# mainboard.net
KiCad netlist of a schematic drawn in EAGLE
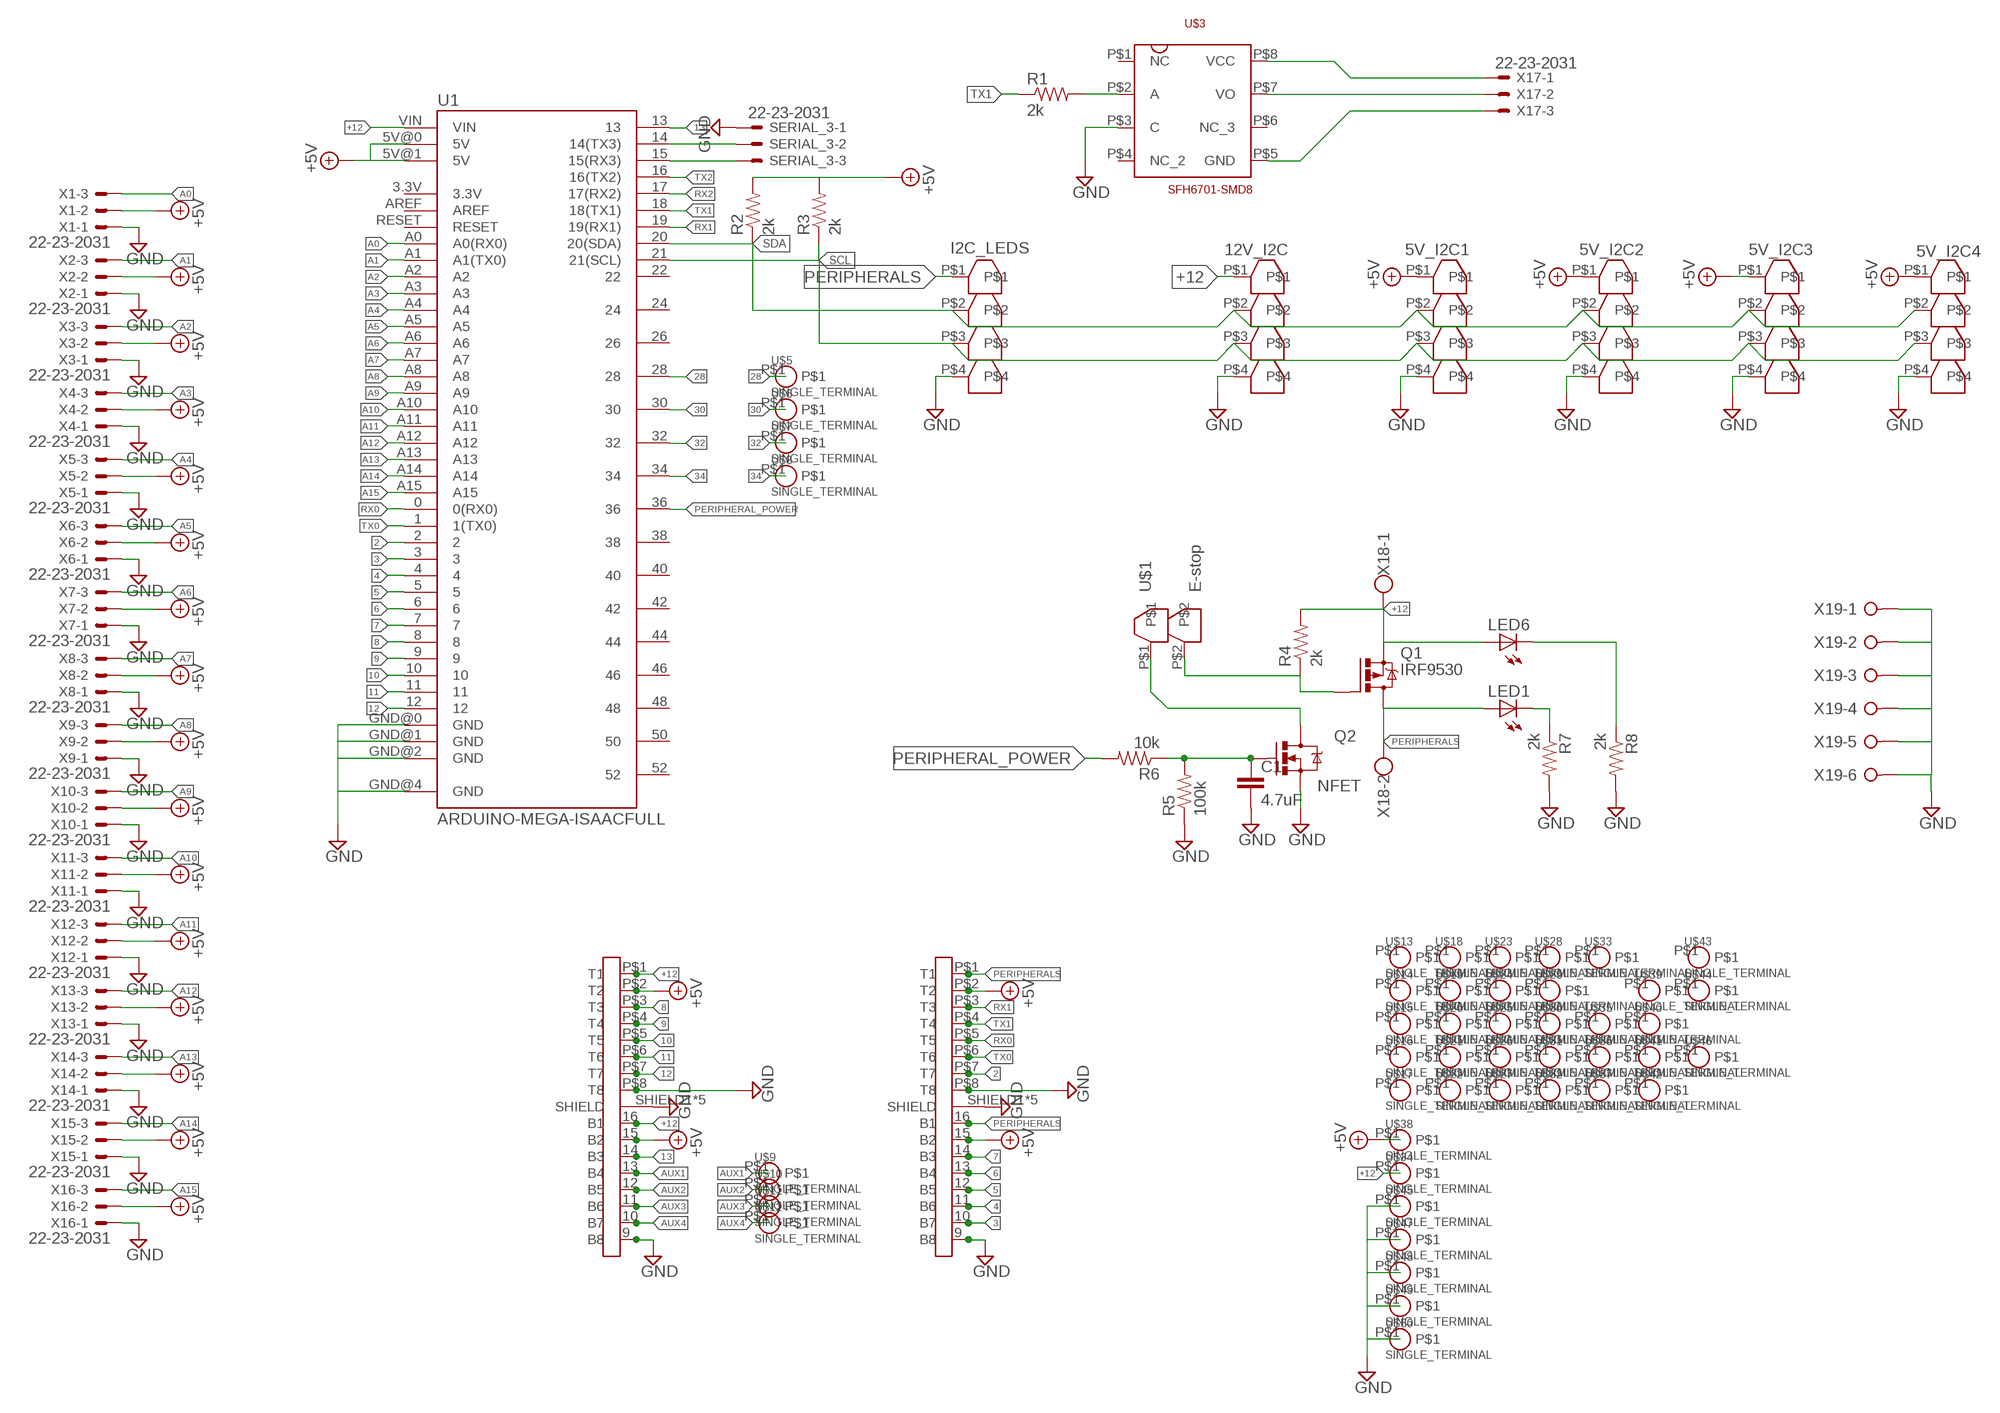
[diagram p0: schematic, sheet 1]

(export (version "E")
  (design (tool "Eeschema 10.0.6"))
  (components
    (comp (ref "5V_I2C1")
      (value "SCREW_TERMINAL_4")
      (footprint "eagle-import:SCREW_TERMINAL_4")
      (libsource (lib "eagle-import") (part "SCREW_TERMINAL_4"))
    )
    (comp (ref "5V_I2C2")
      (value "SCREW_TERMINAL_4")
      (footprint "eagle-import:SCREW_TERMINAL_4")
      (libsource (lib "eagle-import") (part "SCREW_TERMINAL_4"))
    )
    (comp (ref "5V_I2C3")
      (value "SCREW_TERMINAL_4")
      (footprint "eagle-import:SCREW_TERMINAL_4")
      (libsource (lib "eagle-import") (part "SCREW_TERMINAL_4"))
    )
    (comp (ref "5V_I2C4")
      (value "SCREW_TERMINAL_4")
      (footprint "eagle-import:SCREW_TERMINAL_4")
      (libsource (lib "eagle-import") (part "SCREW_TERMINAL_4"))
    )
    (comp (ref "12V_I2C")
      (value "SCREW_TERMINAL_4")
      (footprint "eagle-import:SCREW_TERMINAL_4")
      (libsource (lib "eagle-import") (part "SCREW_TERMINAL_4"))
    )
    (comp (ref "C1")
      (value "4.7uF")
      (footprint "eagle-import:C0603")
      (libsource (lib "eagle-import") (part "C-EUC0603"))
    )
    (comp (ref "I2C_LEDS")
      (value "SCREW_TERMINAL_4")
      (footprint "eagle-import:SCREW_TERMINAL_4")
      (libsource (lib "eagle-import") (part "SCREW_TERMINAL_4"))
    )
    (comp (ref "LED1")
      (value "LED0603")
      (footprint "eagle-import:LED-0603")
      (libsource (lib "eagle-import") (part "LED0603"))
    )
    (comp (ref "LED6")
      (value "LED0603")
      (footprint "eagle-import:LED-0603")
      (libsource (lib "eagle-import") (part "LED0603"))
    )
    (comp (ref "Q1")
      (value "IRF9530")
      (footprint "eagle-import:TO220BV")
      (libsource (lib "eagle-import") (part "IRF9530"))
    )
    (comp (ref "Q2")
      (value "NFET")
      (footprint "eagle-import:SOT23")
      (libsource (lib "eagle-import") (part "MOSFET-NCHANNELBSS123LT1G"))
    )
    (comp (ref "R1")
      (value "2k")
      (footprint "eagle-import:0603-RES")
      (libsource (lib "eagle-import") (part "RESISTOR0603-RES"))
    )
    (comp (ref "R2")
      (value "2k")
      (footprint "eagle-import:0603-RES")
      (libsource (lib "eagle-import") (part "RESISTOR0603-RES"))
    )
    (comp (ref "R3")
      (value "2k")
      (footprint "eagle-import:0603-RES")
      (libsource (lib "eagle-import") (part "RESISTOR0603-RES"))
    )
    (comp (ref "R4")
      (value "2k")
      (footprint "eagle-import:0603-RES")
      (libsource (lib "eagle-import") (part "RESISTOR0603-RES"))
    )
    (comp (ref "R5")
      (value "100k")
      (footprint "eagle-import:0603-RES")
      (libsource (lib "eagle-import") (part "RESISTOR0603-RES"))
    )
    (comp (ref "R6")
      (value "10k")
      (footprint "eagle-import:0603-RES")
      (libsource (lib "eagle-import") (part "RESISTOR0603-RES"))
    )
    (comp (ref "R7")
      (value "2k")
      (footprint "eagle-import:0603-RES")
      (libsource (lib "eagle-import") (part "RESISTOR0603-RES"))
    )
    (comp (ref "R8")
      (value "2k")
      (footprint "eagle-import:0603-RES")
      (libsource (lib "eagle-import") (part "RESISTOR0603-RES"))
    )
    (comp (ref "SERIAL_3")
      (value "22-23-2031")
      (footprint "eagle-import:22-23-2031")
      (fields
        (field (name "MF") "MOLEX")
        (field (name "MF_1") "MOLEX")
        (field (name "MPN") "22-23-2031")
        (field (name "OC_FARNELL") "1462950")
        (field (name "OC_NEWARK") "30C0862")
      )
      (libsource (lib "eagle-import") (part "22-23-2031"))
    )
    (comp (ref "U$1")
      (value "E-stop")
      (footprint "eagle-import:SCREW_TERMINAL_2")
      (libsource (lib "eagle-import") (part "SCREW_TERMINAL_2"))
    )
    (comp (ref "U$2")
      (value "RJ45-DUAL-STACKED")
      (footprint "eagle-import:RJ45-DUAL-10118096")
      (libsource (lib "eagle-import") (part "RJ45-DUAL-STACKED"))
    )
    (comp (ref "U$3")
      (value "SFH6701-SMD8")
      (footprint "eagle-import:8-SMD-GULLWING")
      (libsource (lib "eagle-import") (part "SFH6701-SMD8"))
    )
    (comp (ref "U$4")
      (value "RJ45-DUAL-STACKED")
      (footprint "eagle-import:RJ45-DUAL-10118096")
      (libsource (lib "eagle-import") (part "RJ45-DUAL-STACKED"))
    )
    (comp (ref "U$5")
      (value "SINGLE_TERMINAL")
      (footprint "eagle-import:PLATED_HOLE")
      (libsource (lib "eagle-import") (part "SINGLE_TERMINAL"))
    )
    (comp (ref "U$6")
      (value "SINGLE_TERMINAL")
      (footprint "eagle-import:PLATED_HOLE")
      (libsource (lib "eagle-import") (part "SINGLE_TERMINAL"))
    )
    (comp (ref "U$7")
      (value "SINGLE_TERMINAL")
      (footprint "eagle-import:PLATED_HOLE")
      (libsource (lib "eagle-import") (part "SINGLE_TERMINAL"))
    )
    (comp (ref "U$8")
      (value "SINGLE_TERMINAL")
      (footprint "eagle-import:PLATED_HOLE")
      (libsource (lib "eagle-import") (part "SINGLE_TERMINAL"))
    )
    (comp (ref "U$9")
      (value "SINGLE_TERMINAL")
      (footprint "eagle-import:PLATED_HOLE")
      (libsource (lib "eagle-import") (part "SINGLE_TERMINAL"))
    )
    (comp (ref "U$10")
      (value "SINGLE_TERMINAL")
      (footprint "eagle-import:PLATED_HOLE")
      (libsource (lib "eagle-import") (part "SINGLE_TERMINAL"))
    )
    (comp (ref "U$11")
      (value "SINGLE_TERMINAL")
      (footprint "eagle-import:PLATED_HOLE")
      (libsource (lib "eagle-import") (part "SINGLE_TERMINAL"))
    )
    (comp (ref "U$12")
      (value "SINGLE_TERMINAL")
      (footprint "eagle-import:PLATED_HOLE")
      (libsource (lib "eagle-import") (part "SINGLE_TERMINAL"))
    )
    (comp (ref "U$13")
      (value "SINGLE_TERMINAL")
      (footprint "eagle-import:PLATED_HOLE")
      (libsource (lib "eagle-import") (part "SINGLE_TERMINAL"))
    )
    (comp (ref "U$14")
      (value "SINGLE_TERMINAL")
      (footprint "eagle-import:PLATED_HOLE")
      (libsource (lib "eagle-import") (part "SINGLE_TERMINAL"))
    )
    (comp (ref "U$15")
      (value "SINGLE_TERMINAL")
      (footprint "eagle-import:PLATED_HOLE")
      (libsource (lib "eagle-import") (part "SINGLE_TERMINAL"))
    )
    (comp (ref "U$16")
      (value "SINGLE_TERMINAL")
      (footprint "eagle-import:PLATED_HOLE")
      (libsource (lib "eagle-import") (part "SINGLE_TERMINAL"))
    )
    (comp (ref "U$17")
      (value "SINGLE_TERMINAL")
      (footprint "eagle-import:PLATED_HOLE")
      (libsource (lib "eagle-import") (part "SINGLE_TERMINAL"))
    )
    (comp (ref "U$18")
      (value "SINGLE_TERMINAL")
      (footprint "eagle-import:PLATED_HOLE")
      (libsource (lib "eagle-import") (part "SINGLE_TERMINAL"))
    )
    (comp (ref "U$19")
      (value "SINGLE_TERMINAL")
      (footprint "eagle-import:PLATED_HOLE")
      (libsource (lib "eagle-import") (part "SINGLE_TERMINAL"))
    )
    (comp (ref "U$20")
      (value "SINGLE_TERMINAL")
      (footprint "eagle-import:PLATED_HOLE")
      (libsource (lib "eagle-import") (part "SINGLE_TERMINAL"))
    )
    (comp (ref "U$21")
      (value "SINGLE_TERMINAL")
      (footprint "eagle-import:PLATED_HOLE")
      (libsource (lib "eagle-import") (part "SINGLE_TERMINAL"))
    )
    (comp (ref "U$22")
      (value "SINGLE_TERMINAL")
      (footprint "eagle-import:PLATED_HOLE")
      (libsource (lib "eagle-import") (part "SINGLE_TERMINAL"))
    )
    (comp (ref "U$23")
      (value "SINGLE_TERMINAL")
      (footprint "eagle-import:PLATED_HOLE")
      (libsource (lib "eagle-import") (part "SINGLE_TERMINAL"))
    )
    (comp (ref "U$24")
      (value "SINGLE_TERMINAL")
      (footprint "eagle-import:PLATED_HOLE")
      (libsource (lib "eagle-import") (part "SINGLE_TERMINAL"))
    )
    (comp (ref "U$25")
      (value "SINGLE_TERMINAL")
      (footprint "eagle-import:PLATED_HOLE")
      (libsource (lib "eagle-import") (part "SINGLE_TERMINAL"))
    )
    (comp (ref "U$26")
      (value "SINGLE_TERMINAL")
      (footprint "eagle-import:PLATED_HOLE")
      (libsource (lib "eagle-import") (part "SINGLE_TERMINAL"))
    )
    (comp (ref "U$27")
      (value "SINGLE_TERMINAL")
      (footprint "eagle-import:PLATED_HOLE")
      (libsource (lib "eagle-import") (part "SINGLE_TERMINAL"))
    )
    (comp (ref "U$28")
      (value "SINGLE_TERMINAL")
      (footprint "eagle-import:PLATED_HOLE")
      (libsource (lib "eagle-import") (part "SINGLE_TERMINAL"))
    )
    (comp (ref "U$29")
      (value "SINGLE_TERMINAL")
      (footprint "eagle-import:PLATED_HOLE")
      (libsource (lib "eagle-import") (part "SINGLE_TERMINAL"))
    )
    (comp (ref "U$30")
      (value "SINGLE_TERMINAL")
      (footprint "eagle-import:PLATED_HOLE")
      (libsource (lib "eagle-import") (part "SINGLE_TERMINAL"))
    )
    (comp (ref "U$31")
      (value "SINGLE_TERMINAL")
      (footprint "eagle-import:PLATED_HOLE")
      (libsource (lib "eagle-import") (part "SINGLE_TERMINAL"))
    )
    (comp (ref "U$32")
      (value "SINGLE_TERMINAL")
      (footprint "eagle-import:PLATED_HOLE")
      (libsource (lib "eagle-import") (part "SINGLE_TERMINAL"))
    )
    (comp (ref "U$33")
      (value "SINGLE_TERMINAL")
      (footprint "eagle-import:PLATED_HOLE")
      (libsource (lib "eagle-import") (part "SINGLE_TERMINAL"))
    )
    (comp (ref "U$34")
      (value "SINGLE_TERMINAL")
      (footprint "eagle-import:PLATED_HOLE")
      (libsource (lib "eagle-import") (part "SINGLE_TERMINAL"))
    )
    (comp (ref "U$35")
      (value "SINGLE_TERMINAL")
      (footprint "eagle-import:PLATED_HOLE")
      (libsource (lib "eagle-import") (part "SINGLE_TERMINAL"))
    )
    (comp (ref "U$36")
      (value "SINGLE_TERMINAL")
      (footprint "eagle-import:PLATED_HOLE")
      (libsource (lib "eagle-import") (part "SINGLE_TERMINAL"))
    )
    (comp (ref "U$37")
      (value "SINGLE_TERMINAL")
      (footprint "eagle-import:PLATED_HOLE")
      (libsource (lib "eagle-import") (part "SINGLE_TERMINAL"))
    )
    (comp (ref "U$38")
      (value "SINGLE_TERMINAL")
      (footprint "eagle-import:PLATED_HOLE")
      (libsource (lib "eagle-import") (part "SINGLE_TERMINAL"))
    )
    (comp (ref "U$39")
      (value "SINGLE_TERMINAL")
      (footprint "eagle-import:PLATED_HOLE")
      (libsource (lib "eagle-import") (part "SINGLE_TERMINAL"))
    )
    (comp (ref "U$40")
      (value "SINGLE_TERMINAL")
      (footprint "eagle-import:PLATED_HOLE")
      (libsource (lib "eagle-import") (part "SINGLE_TERMINAL"))
    )
    (comp (ref "U$41")
      (value "SINGLE_TERMINAL")
      (footprint "eagle-import:PLATED_HOLE")
      (libsource (lib "eagle-import") (part "SINGLE_TERMINAL"))
    )
    (comp (ref "U$42")
      (value "SINGLE_TERMINAL")
      (footprint "eagle-import:PLATED_HOLE")
      (libsource (lib "eagle-import") (part "SINGLE_TERMINAL"))
    )
    (comp (ref "U$43")
      (value "SINGLE_TERMINAL")
      (footprint "eagle-import:PLATED_HOLE")
      (libsource (lib "eagle-import") (part "SINGLE_TERMINAL"))
    )
    (comp (ref "U$44")
      (value "SINGLE_TERMINAL")
      (footprint "eagle-import:PLATED_HOLE")
      (libsource (lib "eagle-import") (part "SINGLE_TERMINAL"))
    )
    (comp (ref "U$45")
      (value "SINGLE_TERMINAL")
      (footprint "eagle-import:PLATED_HOLE")
      (libsource (lib "eagle-import") (part "SINGLE_TERMINAL"))
    )
    (comp (ref "U$46")
      (value "SINGLE_TERMINAL")
      (footprint "eagle-import:PLATED_HOLE")
      (libsource (lib "eagle-import") (part "SINGLE_TERMINAL"))
    )
    (comp (ref "U$47")
      (value "SINGLE_TERMINAL")
      (footprint "eagle-import:PLATED_HOLE")
      (libsource (lib "eagle-import") (part "SINGLE_TERMINAL"))
    )
    (comp (ref "U$48")
      (value "SINGLE_TERMINAL")
      (footprint "eagle-import:PLATED_HOLE")
      (libsource (lib "eagle-import") (part "SINGLE_TERMINAL"))
    )
    (comp (ref "U$49")
      (value "SINGLE_TERMINAL")
      (footprint "eagle-import:PLATED_HOLE")
      (libsource (lib "eagle-import") (part "SINGLE_TERMINAL"))
    )
    (comp (ref "U$50")
      (value "SINGLE_TERMINAL")
      (footprint "eagle-import:PLATED_HOLE")
      (libsource (lib "eagle-import") (part "SINGLE_TERMINAL"))
    )
    (comp (ref "U1")
      (value "ARDUINO-MEGA-ISAACFULL")
      (footprint "eagle-import:ARDUINO_MEGA_ISAAC")
      (libsource (lib "eagle-import") (part "ARDUINO-MEGA-ISAACFULL"))
    )
    (comp (ref "X1")
      (value "22-23-2031")
      (footprint "eagle-import:22-23-2031")
      (fields (field (name "MF") "MOLEX"))
      (libsource (lib "eagle-import") (part "22-23-2031"))
    )
    (comp (ref "X2")
      (value "22-23-2031")
      (footprint "eagle-import:22-23-2031")
      (fields (field (name "MF") "MOLEX"))
      (libsource (lib "eagle-import") (part "22-23-2031"))
    )
    (comp (ref "X3")
      (value "22-23-2031")
      (footprint "eagle-import:22-23-2031")
      (fields (field (name "MF") "MOLEX"))
      (libsource (lib "eagle-import") (part "22-23-2031"))
    )
    (comp (ref "X4")
      (value "22-23-2031")
      (footprint "eagle-import:22-23-2031")
      (fields (field (name "MF") "MOLEX"))
      (libsource (lib "eagle-import") (part "22-23-2031"))
    )
    (comp (ref "X5")
      (value "22-23-2031")
      (footprint "eagle-import:22-23-2031")
      (fields (field (name "MF") "MOLEX"))
      (libsource (lib "eagle-import") (part "22-23-2031"))
    )
    (comp (ref "X6")
      (value "22-23-2031")
      (footprint "eagle-import:22-23-2031")
      (fields (field (name "MF") "MOLEX"))
      (libsource (lib "eagle-import") (part "22-23-2031"))
    )
    (comp (ref "X7")
      (value "22-23-2031")
      (footprint "eagle-import:22-23-2031")
      (fields (field (name "MF") "MOLEX"))
      (libsource (lib "eagle-import") (part "22-23-2031"))
    )
    (comp (ref "X8")
      (value "22-23-2031")
      (footprint "eagle-import:22-23-2031")
      (fields (field (name "MF") "MOLEX"))
      (libsource (lib "eagle-import") (part "22-23-2031"))
    )
    (comp (ref "X9")
      (value "22-23-2031")
      (footprint "eagle-import:22-23-2031")
      (fields (field (name "MF") "MOLEX"))
      (libsource (lib "eagle-import") (part "22-23-2031"))
    )
    (comp (ref "X10")
      (value "22-23-2031")
      (footprint "eagle-import:22-23-2031")
      (fields (field (name "MF") "MOLEX"))
      (libsource (lib "eagle-import") (part "22-23-2031"))
    )
    (comp (ref "X11")
      (value "22-23-2031")
      (footprint "eagle-import:22-23-2031")
      (fields (field (name "MF") "MOLEX"))
      (libsource (lib "eagle-import") (part "22-23-2031"))
    )
    (comp (ref "X12")
      (value "22-23-2031")
      (footprint "eagle-import:22-23-2031")
      (fields (field (name "MF") "MOLEX"))
      (libsource (lib "eagle-import") (part "22-23-2031"))
    )
    (comp (ref "X13")
      (value "22-23-2031")
      (footprint "eagle-import:22-23-2031")
      (fields (field (name "MF") "MOLEX"))
      (libsource (lib "eagle-import") (part "22-23-2031"))
    )
    (comp (ref "X14")
      (value "22-23-2031")
      (footprint "eagle-import:22-23-2031")
      (fields (field (name "MF") "MOLEX"))
      (libsource (lib "eagle-import") (part "22-23-2031"))
    )
    (comp (ref "X15")
      (value "22-23-2031")
      (footprint "eagle-import:22-23-2031")
      (fields (field (name "MF") "MOLEX"))
      (libsource (lib "eagle-import") (part "22-23-2031"))
    )
    (comp (ref "X16")
      (value "22-23-2031")
      (footprint "eagle-import:22-23-2031")
      (fields (field (name "MF") "MOLEX"))
      (libsource (lib "eagle-import") (part "22-23-2031"))
    )
    (comp (ref "X17")
      (value "22-23-2031")
      (footprint "eagle-import:22-23-2031")
      (fields
        (field (name "MF") "MOLEX")
        (field (name "MF_1") "MOLEX")
        (field (name "MPN") "22-23-2031")
        (field (name "OC_FARNELL") "1462950")
        (field (name "OC_NEWARK") "30C0862")
      )
      (libsource (lib "eagle-import") (part "22-23-2031"))
    )
    (comp (ref "X18")
      (value "W237-102")
      (footprint "eagle-import:W237-102")
      (fields (field (name "MPN") "237-102"))
      (libsource (lib "eagle-import") (part "W237-102"))
    )
    (comp (ref "X19")
      (value "W237-06P")
      (footprint "eagle-import:W237-6P")
      (libsource (lib "eagle-import") (part "W237-06P"))
    )
  )
  (nets
    (net (code "1") (name "+5V") (class "Default")
      (node (ref "5V_I2C1") (pin "P$1") (pinfunction "P$1_P$1") (pintype "bidirectional"))
      (node (ref "5V_I2C2") (pin "P$1") (pinfunction "P$1_P$1") (pintype "bidirectional"))
      (node (ref "5V_I2C3") (pin "P$1") (pinfunction "P$1_P$1") (pintype "bidirectional"))
      (node (ref "5V_I2C4") (pin "P$1") (pinfunction "P$1_P$1") (pintype "bidirectional"))
      (node (ref "R2") (pin "2") (pinfunction "2_2") (pintype "passive"))
      (node (ref "R3") (pin "2") (pinfunction "2_2") (pintype "passive"))
      (node (ref "U$2") (pin "15") (pinfunction "B2_15") (pintype "bidirectional"))
      (node (ref "U$2") (pin "P$2") (pinfunction "T2_P$2") (pintype "bidirectional"))
      (node (ref "U$38") (pin "P$1") (pinfunction "P$1_P$1") (pintype "bidirectional"))
      (node (ref "U$4") (pin "15") (pinfunction "B2_15") (pintype "bidirectional"))
      (node (ref "U$4") (pin "P$2") (pinfunction "T2_P$2") (pintype "bidirectional"))
      (node (ref "U1") (pin "5V@0") (pinfunction "5V_5V@0") (pintype "bidirectional"))
      (node (ref "U1") (pin "5V@1") (pinfunction "5V_5V@1") (pintype "bidirectional"))
      (node (ref "X1") (pin "2") (pinfunction "S_2") (pintype "passive"))
      (node (ref "X10") (pin "2") (pinfunction "S_2") (pintype "passive"))
      (node (ref "X11") (pin "2") (pinfunction "S_2") (pintype "passive"))
      (node (ref "X12") (pin "2") (pinfunction "S_2") (pintype "passive"))
      (node (ref "X13") (pin "2") (pinfunction "S_2") (pintype "passive"))
      (node (ref "X14") (pin "2") (pinfunction "S_2") (pintype "passive"))
      (node (ref "X15") (pin "2") (pinfunction "S_2") (pintype "passive"))
      (node (ref "X16") (pin "2") (pinfunction "S_2") (pintype "passive"))
      (node (ref "X2") (pin "2") (pinfunction "S_2") (pintype "passive"))
      (node (ref "X3") (pin "2") (pinfunction "S_2") (pintype "passive"))
      (node (ref "X4") (pin "2") (pinfunction "S_2") (pintype "passive"))
      (node (ref "X5") (pin "2") (pinfunction "S_2") (pintype "passive"))
      (node (ref "X6") (pin "2") (pinfunction "S_2") (pintype "passive"))
      (node (ref "X7") (pin "2") (pinfunction "S_2") (pintype "passive"))
      (node (ref "X8") (pin "2") (pinfunction "S_2") (pintype "passive"))
      (node (ref "X9") (pin "2") (pinfunction "S_2") (pintype "passive"))
    )
    (net (code "2") (name "+12") (class "Default")
      (node (ref "12V_I2C") (pin "P$1") (pinfunction "P$1_P$1") (pintype "bidirectional"))
      (node (ref "LED6") (pin "A") (pinfunction "A_A") (pintype "passive"))
      (node (ref "Q1") (pin "S") (pinfunction "S_S") (pintype "passive"))
      (node (ref "R4") (pin "2") (pinfunction "2_2") (pintype "passive"))
      (node (ref "U$2") (pin "16") (pinfunction "B1_16") (pintype "bidirectional"))
      (node (ref "U$2") (pin "P$1") (pinfunction "T1_P$1") (pintype "bidirectional"))
      (node (ref "U$34") (pin "P$1") (pinfunction "P$1_P$1") (pintype "bidirectional"))
      (node (ref "U1") (pin "VIN") (pinfunction "VIN_VIN") (pintype "bidirectional"))
      (node (ref "X18") (pin "1") (pinfunction "KL_1") (pintype "passive"))
    )
    (net (code "3") (name "2") (class "Default")
      (node (ref "U$4") (pin "P$7") (pinfunction "T7_P$7") (pintype "bidirectional"))
      (node (ref "U1") (pin "2") (pinfunction "2_2") (pintype "bidirectional"))
    )
    (net (code "4") (name "3") (class "Default")
      (node (ref "U$4") (pin "10") (pinfunction "B7_10") (pintype "bidirectional"))
      (node (ref "U1") (pin "3") (pinfunction "3_3") (pintype "bidirectional"))
    )
    (net (code "5") (name "4") (class "Default")
      (node (ref "U$4") (pin "11") (pinfunction "B6_11") (pintype "bidirectional"))
      (node (ref "U1") (pin "4") (pinfunction "4_4") (pintype "bidirectional"))
    )
    (net (code "6") (name "5") (class "Default")
      (node (ref "U$4") (pin "12") (pinfunction "B5_12") (pintype "bidirectional"))
      (node (ref "U1") (pin "5") (pinfunction "5_5") (pintype "bidirectional"))
    )
    (net (code "7") (name "6") (class "Default")
      (node (ref "U$4") (pin "13") (pinfunction "B4_13") (pintype "bidirectional"))
      (node (ref "U1") (pin "6") (pinfunction "6_6") (pintype "bidirectional"))
    )
    (net (code "8") (name "7") (class "Default")
      (node (ref "U$4") (pin "14") (pinfunction "B3_14") (pintype "bidirectional"))
      (node (ref "U1") (pin "7") (pinfunction "7_7") (pintype "bidirectional"))
    )
    (net (code "9") (name "8") (class "Default")
      (node (ref "U$2") (pin "P$3") (pinfunction "T3_P$3") (pintype "bidirectional"))
      (node (ref "U1") (pin "8") (pinfunction "8_8") (pintype "bidirectional"))
    )
    (net (code "10") (name "9") (class "Default")
      (node (ref "U$2") (pin "P$4") (pinfunction "T4_P$4") (pintype "bidirectional"))
      (node (ref "U1") (pin "9") (pinfunction "9_9") (pintype "bidirectional"))
    )
    (net (code "11") (name "10") (class "Default")
      (node (ref "U$2") (pin "P$5") (pinfunction "T5_P$5") (pintype "bidirectional"))
      (node (ref "U1") (pin "10") (pinfunction "10_10") (pintype "bidirectional"))
    )
    (net (code "12") (name "11") (class "Default")
      (node (ref "U$2") (pin "P$6") (pinfunction "T6_P$6") (pintype "bidirectional"))
      (node (ref "U1") (pin "11") (pinfunction "11_11") (pintype "bidirectional"))
    )
    (net (code "13") (name "12") (class "Default")
      (node (ref "U$2") (pin "P$7") (pinfunction "T7_P$7") (pintype "bidirectional"))
      (node (ref "U1") (pin "12") (pinfunction "12_12") (pintype "bidirectional"))
    )
    (net (code "14") (name "13") (class "Default")
      (node (ref "U$2") (pin "14") (pinfunction "B3_14") (pintype "bidirectional"))
      (node (ref "U1") (pin "13") (pinfunction "13_13") (pintype "bidirectional"))
    )
    (net (code "15") (name "28") (class "Default")
      (node (ref "U$5") (pin "P$1") (pinfunction "P$1_P$1") (pintype "bidirectional"))
      (node (ref "U1") (pin "28") (pinfunction "28_28") (pintype "bidirectional"))
    )
    (net (code "16") (name "30") (class "Default")
      (node (ref "U$6") (pin "P$1") (pinfunction "P$1_P$1") (pintype "bidirectional"))
      (node (ref "U1") (pin "30") (pinfunction "30_30") (pintype "bidirectional"))
    )
    (net (code "17") (name "32") (class "Default")
      (node (ref "U$7") (pin "P$1") (pinfunction "P$1_P$1") (pintype "bidirectional"))
      (node (ref "U1") (pin "32") (pinfunction "32_32") (pintype "bidirectional"))
    )
    (net (code "18") (name "34") (class "Default")
      (node (ref "U$8") (pin "P$1") (pinfunction "P$1_P$1") (pintype "bidirectional"))
      (node (ref "U1") (pin "34") (pinfunction "34_34") (pintype "bidirectional"))
    )
    (net (code "19") (name "A0") (class "Default")
      (node (ref "U1") (pin "A0") (pinfunction "A0(RX0)_A0") (pintype "bidirectional"))
      (node (ref "X1") (pin "3") (pinfunction "S_3") (pintype "passive"))
    )
    (net (code "20") (name "A1") (class "Default")
      (node (ref "U1") (pin "A1") (pinfunction "A1(TX0)_A1") (pintype "bidirectional"))
      (node (ref "X2") (pin "3") (pinfunction "S_3") (pintype "passive"))
    )
    (net (code "21") (name "A2") (class "Default")
      (node (ref "U1") (pin "A2") (pinfunction "A2_A2") (pintype "bidirectional"))
      (node (ref "X3") (pin "3") (pinfunction "S_3") (pintype "passive"))
    )
    (net (code "22") (name "A3") (class "Default")
      (node (ref "U1") (pin "A3") (pinfunction "A3_A3") (pintype "bidirectional"))
      (node (ref "X4") (pin "3") (pinfunction "S_3") (pintype "passive"))
    )
    (net (code "23") (name "A4") (class "Default")
      (node (ref "U1") (pin "A4") (pinfunction "A4_A4") (pintype "bidirectional"))
      (node (ref "X5") (pin "3") (pinfunction "S_3") (pintype "passive"))
    )
    (net (code "24") (name "A5") (class "Default")
      (node (ref "U1") (pin "A5") (pinfunction "A5_A5") (pintype "bidirectional"))
      (node (ref "X6") (pin "3") (pinfunction "S_3") (pintype "passive"))
    )
    (net (code "25") (name "A6") (class "Default")
      (node (ref "U1") (pin "A6") (pinfunction "A6_A6") (pintype "bidirectional"))
      (node (ref "X7") (pin "3") (pinfunction "S_3") (pintype "passive"))
    )
    (net (code "26") (name "A7") (class "Default")
      (node (ref "U1") (pin "A7") (pinfunction "A7_A7") (pintype "bidirectional"))
      (node (ref "X8") (pin "3") (pinfunction "S_3") (pintype "passive"))
    )
    (net (code "27") (name "A8") (class "Default")
      (node (ref "U1") (pin "A8") (pinfunction "A8_A8") (pintype "bidirectional"))
      (node (ref "X9") (pin "3") (pinfunction "S_3") (pintype "passive"))
    )
    (net (code "28") (name "A9") (class "Default")
      (node (ref "U1") (pin "A9") (pinfunction "A9_A9") (pintype "bidirectional"))
      (node (ref "X10") (pin "3") (pinfunction "S_3") (pintype "passive"))
    )
    (net (code "29") (name "A10") (class "Default")
      (node (ref "U1") (pin "A10") (pinfunction "A10_A10") (pintype "bidirectional"))
      (node (ref "X11") (pin "3") (pinfunction "S_3") (pintype "passive"))
    )
    (net (code "30") (name "A11") (class "Default")
      (node (ref "U1") (pin "A11") (pinfunction "A11_A11") (pintype "bidirectional"))
      (node (ref "X12") (pin "3") (pinfunction "S_3") (pintype "passive"))
    )
    (net (code "31") (name "A12") (class "Default")
      (node (ref "U1") (pin "A12") (pinfunction "A12_A12") (pintype "bidirectional"))
      (node (ref "X13") (pin "3") (pinfunction "S_3") (pintype "passive"))
    )
    (net (code "32") (name "A13") (class "Default")
      (node (ref "U1") (pin "A13") (pinfunction "A13_A13") (pintype "bidirectional"))
      (node (ref "X14") (pin "3") (pinfunction "S_3") (pintype "passive"))
    )
    (net (code "33") (name "A14") (class "Default")
      (node (ref "U1") (pin "A14") (pinfunction "A14_A14") (pintype "bidirectional"))
      (node (ref "X15") (pin "3") (pinfunction "S_3") (pintype "passive"))
    )
    (net (code "34") (name "A15") (class "Default")
      (node (ref "U1") (pin "A15") (pinfunction "A15_A15") (pintype "bidirectional"))
      (node (ref "X16") (pin "3") (pinfunction "S_3") (pintype "passive"))
    )
    (net (code "35") (name "AUX1") (class "Default")
      (node (ref "U$2") (pin "13") (pinfunction "B4_13") (pintype "bidirectional"))
      (node (ref "U$9") (pin "P$1") (pinfunction "P$1_P$1") (pintype "bidirectional"))
    )
    (net (code "36") (name "AUX2") (class "Default")
      (node (ref "U$10") (pin "P$1") (pinfunction "P$1_P$1") (pintype "bidirectional"))
      (node (ref "U$2") (pin "12") (pinfunction "B5_12") (pintype "bidirectional"))
    )
    (net (code "37") (name "AUX3") (class "Default")
      (node (ref "U$11") (pin "P$1") (pinfunction "P$1_P$1") (pintype "bidirectional"))
      (node (ref "U$2") (pin "11") (pinfunction "B6_11") (pintype "bidirectional"))
    )
    (net (code "38") (name "AUX4") (class "Default")
      (node (ref "U$12") (pin "P$1") (pinfunction "P$1_P$1") (pintype "bidirectional"))
      (node (ref "U$2") (pin "10") (pinfunction "B7_10") (pintype "bidirectional"))
    )
    (net (code "39") (name "GND") (class "Default")
      (node (ref "12V_I2C") (pin "P$4") (pinfunction "P$4_P$4") (pintype "bidirectional"))
      (node (ref "5V_I2C1") (pin "P$4") (pinfunction "P$4_P$4") (pintype "bidirectional"))
      (node (ref "5V_I2C2") (pin "P$4") (pinfunction "P$4_P$4") (pintype "bidirectional"))
      (node (ref "5V_I2C3") (pin "P$4") (pinfunction "P$4_P$4") (pintype "bidirectional"))
      (node (ref "5V_I2C4") (pin "P$4") (pinfunction "P$4_P$4") (pintype "bidirectional"))
      (node (ref "C1") (pin "2") (pinfunction "2_2") (pintype "passive"))
      (node (ref "I2C_LEDS") (pin "P$4") (pinfunction "P$4_P$4") (pintype "bidirectional"))
      (node (ref "Q2") (pin "2") (pinfunction "S_2") (pintype "passive"))
      (node (ref "R5") (pin "1") (pinfunction "1_1") (pintype "passive"))
      (node (ref "R7") (pin "2") (pinfunction "2_2") (pintype "passive"))
      (node (ref "R8") (pin "2") (pinfunction "2_2") (pintype "passive"))
      (node (ref "SERIAL_3") (pin "1") (pinfunction "S_1") (pintype "passive"))
      (node (ref "U$2") (pin "9") (pinfunction "B8_9") (pintype "bidirectional"))
      (node (ref "U$2") (pin "P$8") (pinfunction "T8_P$8") (pintype "bidirectional"))
      (node (ref "U$2") (pin "SHIELD1") (pinfunction "SHIELD_SHIELD1") (pintype "bidirectional"))
      (node (ref "U$2") (pin "SHIELD2") (pinfunction "SHIELD_SHIELD2") (pintype "bidirectional"))
      (node (ref "U$2") (pin "SHIELD3") (pinfunction "SHIELD_SHIELD3") (pintype "bidirectional"))
      (node (ref "U$2") (pin "SHIELD4") (pinfunction "SHIELD_SHIELD4") (pintype "bidirectional"))
      (node (ref "U$2") (pin "SHIELD5") (pinfunction "SHIELD_SHIELD5") (pintype "bidirectional"))
      (node (ref "U$3") (pin "P$3") (pinfunction "C_P$3") (pintype "bidirectional"))
      (node (ref "U$4") (pin "9") (pinfunction "B8_9") (pintype "bidirectional"))
      (node (ref "U$4") (pin "P$8") (pinfunction "T8_P$8") (pintype "bidirectional"))
      (node (ref "U$4") (pin "SHIELD1") (pinfunction "SHIELD_SHIELD1") (pintype "bidirectional"))
      (node (ref "U$4") (pin "SHIELD2") (pinfunction "SHIELD_SHIELD2") (pintype "bidirectional"))
      (node (ref "U$4") (pin "SHIELD3") (pinfunction "SHIELD_SHIELD3") (pintype "bidirectional"))
      (node (ref "U$4") (pin "SHIELD4") (pinfunction "SHIELD_SHIELD4") (pintype "bidirectional"))
      (node (ref "U$4") (pin "SHIELD5") (pinfunction "SHIELD_SHIELD5") (pintype "bidirectional"))
      (node (ref "U$45") (pin "P$1") (pinfunction "P$1_P$1") (pintype "bidirectional"))
      (node (ref "U$47") (pin "P$1") (pinfunction "P$1_P$1") (pintype "bidirectional"))
      (node (ref "U$48") (pin "P$1") (pinfunction "P$1_P$1") (pintype "bidirectional"))
      (node (ref "U$49") (pin "P$1") (pinfunction "P$1_P$1") (pintype "bidirectional"))
      (node (ref "U$50") (pin "P$1") (pinfunction "P$1_P$1") (pintype "bidirectional"))
      (node (ref "U1") (pin "GND@0") (pinfunction "GND_GND@0") (pintype "bidirectional"))
      (node (ref "U1") (pin "GND@1") (pinfunction "GND_GND@1") (pintype "bidirectional"))
      (node (ref "U1") (pin "GND@2") (pinfunction "GND_GND@2") (pintype "bidirectional"))
      (node (ref "U1") (pin "GND@4") (pinfunction "GND_GND@4") (pintype "bidirectional"))
      (node (ref "X1") (pin "1") (pinfunction "S_1") (pintype "passive"))
      (node (ref "X10") (pin "1") (pinfunction "S_1") (pintype "passive"))
      (node (ref "X11") (pin "1") (pinfunction "S_1") (pintype "passive"))
      (node (ref "X12") (pin "1") (pinfunction "S_1") (pintype "passive"))
      (node (ref "X13") (pin "1") (pinfunction "S_1") (pintype "passive"))
      (node (ref "X14") (pin "1") (pinfunction "S_1") (pintype "passive"))
      (node (ref "X15") (pin "1") (pinfunction "S_1") (pintype "passive"))
      (node (ref "X16") (pin "1") (pinfunction "S_1") (pintype "passive"))
      (node (ref "X19") (pin "1") (pinfunction "KL_1") (pintype "passive"))
      (node (ref "X19") (pin "2") (pinfunction "KL_2") (pintype "passive"))
      (node (ref "X19") (pin "3") (pinfunction "KL_3") (pintype "passive"))
      (node (ref "X19") (pin "4") (pinfunction "KL_4") (pintype "passive"))
      (node (ref "X19") (pin "5") (pinfunction "KL_5") (pintype "passive"))
      (node (ref "X19") (pin "6") (pinfunction "KL_6") (pintype "passive"))
      (node (ref "X2") (pin "1") (pinfunction "S_1") (pintype "passive"))
      (node (ref "X3") (pin "1") (pinfunction "S_1") (pintype "passive"))
      (node (ref "X4") (pin "1") (pinfunction "S_1") (pintype "passive"))
      (node (ref "X5") (pin "1") (pinfunction "S_1") (pintype "passive"))
      (node (ref "X6") (pin "1") (pinfunction "S_1") (pintype "passive"))
      (node (ref "X7") (pin "1") (pinfunction "S_1") (pintype "passive"))
      (node (ref "X8") (pin "1") (pinfunction "S_1") (pintype "passive"))
      (node (ref "X9") (pin "1") (pinfunction "S_1") (pintype "passive"))
    )
    (net (code "40") (name "Net-(LED1-PadC)") (class "Default")
      (node (ref "LED1") (pin "C") (pinfunction "C_C") (pintype "passive"))
      (node (ref "R7") (pin "1") (pinfunction "1_1") (pintype "passive"))
    )
    (net (code "41") (name "Net-(LED6-PadC)") (class "Default")
      (node (ref "LED6") (pin "C") (pinfunction "C_C") (pintype "passive"))
      (node (ref "R8") (pin "1") (pinfunction "1_1") (pintype "passive"))
    )
    (net (code "42") (name "Net-(Q1-PadG)") (class "Default")
      (node (ref "Q1") (pin "G") (pinfunction "G_G") (pintype "passive"))
      (node (ref "R4") (pin "1") (pinfunction "1_1") (pintype "passive"))
      (node (ref "U$1") (pin "P$2") (pinfunction "P$2_P$2") (pintype "bidirectional"))
    )
    (net (code "43") (name "Net-(Q2-D)") (class "Default")
      (node (ref "Q2") (pin "3") (pinfunction "D_3") (pintype "passive"))
      (node (ref "U$1") (pin "P$1") (pinfunction "P$1_P$1") (pintype "bidirectional"))
    )
    (net (code "44") (name "Net-(Q2-G)") (class "Default")
      (node (ref "C1") (pin "1") (pinfunction "1_1") (pintype "passive"))
      (node (ref "Q2") (pin "1") (pinfunction "G_1") (pintype "passive"))
      (node (ref "R5") (pin "2") (pinfunction "2_2") (pintype "passive"))
      (node (ref "R6") (pin "1") (pinfunction "1_1") (pintype "passive"))
    )
    (net (code "45") (name "Net-(SERIAL_3B-S)") (class "Default")
      (node (ref "SERIAL_3") (pin "2") (pinfunction "S_2") (pintype "passive"))
      (node (ref "U1") (pin "14") (pinfunction "14(TX3)_14") (pintype "bidirectional"))
    )
    (net (code "46") (name "Net-(SERIAL_3C-S)") (class "Default")
      (node (ref "SERIAL_3") (pin "3") (pinfunction "S_3") (pintype "passive"))
      (node (ref "U1") (pin "15") (pinfunction "15(RX3)_15") (pintype "bidirectional"))
    )
    (net (code "47") (name "Net-(U$3-A)") (class "Default")
      (node (ref "R1") (pin "2") (pinfunction "2_2") (pintype "passive"))
      (node (ref "U$3") (pin "P$2") (pinfunction "A_P$2") (pintype "bidirectional"))
    )
    (net (code "48") (name "Net-(U$3-GND)") (class "Default")
      (node (ref "U$3") (pin "P$5") (pinfunction "GND_P$5") (pintype "bidirectional"))
      (node (ref "X17") (pin "3") (pinfunction "S_3") (pintype "passive"))
    )
    (net (code "49") (name "Net-(U$3-VCC)") (class "Default")
      (node (ref "U$3") (pin "P$8") (pinfunction "VCC_P$8") (pintype "bidirectional"))
      (node (ref "X17") (pin "1") (pinfunction "S_1") (pintype "passive"))
    )
    (net (code "50") (name "Net-(U$3-VO)") (class "Default")
      (node (ref "U$3") (pin "P$7") (pinfunction "VO_P$7") (pintype "bidirectional"))
      (node (ref "X17") (pin "2") (pinfunction "S_2") (pintype "passive"))
    )
    (net (code "51") (name "PERIPHERALS") (class "Default")
      (node (ref "I2C_LEDS") (pin "P$1") (pinfunction "P$1_P$1") (pintype "bidirectional"))
      (node (ref "LED1") (pin "A") (pinfunction "A_A") (pintype "passive"))
      (node (ref "Q1") (pin "D") (pinfunction "D_D") (pintype "passive"))
      (node (ref "U$4") (pin "16") (pinfunction "B1_16") (pintype "bidirectional"))
      (node (ref "U$4") (pin "P$1") (pinfunction "T1_P$1") (pintype "bidirectional"))
      (node (ref "X18") (pin "2") (pinfunction "KL_2") (pintype "passive"))
    )
    (net (code "52") (name "PERIPHERAL_POWER") (class "Default")
      (node (ref "R6") (pin "2") (pinfunction "2_2") (pintype "passive"))
      (node (ref "U1") (pin "36") (pinfunction "36_36") (pintype "bidirectional"))
    )
    (net (code "53") (name "RX0") (class "Default")
      (node (ref "U$4") (pin "P$5") (pinfunction "T5_P$5") (pintype "bidirectional"))
      (node (ref "U1") (pin "0") (pinfunction "0(RX0)_0") (pintype "bidirectional"))
    )
    (net (code "54") (name "RX1") (class "Default")
      (node (ref "U$4") (pin "P$3") (pinfunction "T3_P$3") (pintype "bidirectional"))
      (node (ref "U1") (pin "19") (pinfunction "19(RX1)_19") (pintype "bidirectional"))
    )
    (net (code "55") (name "RX2") (class "Default")
      (node (ref "U1") (pin "17") (pinfunction "17(RX2)_17") (pintype "bidirectional"))
    )
    (net (code "56") (name "SCL") (class "Default")
      (node (ref "12V_I2C") (pin "P$3") (pinfunction "P$3_P$3") (pintype "bidirectional"))
      (node (ref "5V_I2C1") (pin "P$3") (pinfunction "P$3_P$3") (pintype "bidirectional"))
      (node (ref "5V_I2C2") (pin "P$3") (pinfunction "P$3_P$3") (pintype "bidirectional"))
      (node (ref "5V_I2C3") (pin "P$3") (pinfunction "P$3_P$3") (pintype "bidirectional"))
      (node (ref "5V_I2C4") (pin "P$3") (pinfunction "P$3_P$3") (pintype "bidirectional"))
      (node (ref "I2C_LEDS") (pin "P$3") (pinfunction "P$3_P$3") (pintype "bidirectional"))
      (node (ref "R3") (pin "1") (pinfunction "1_1") (pintype "passive"))
      (node (ref "U1") (pin "21") (pinfunction "21(SCL)_21") (pintype "bidirectional"))
    )
    (net (code "57") (name "SDA") (class "Default")
      (node (ref "12V_I2C") (pin "P$2") (pinfunction "P$2_P$2") (pintype "bidirectional"))
      (node (ref "5V_I2C1") (pin "P$2") (pinfunction "P$2_P$2") (pintype "bidirectional"))
      (node (ref "5V_I2C2") (pin "P$2") (pinfunction "P$2_P$2") (pintype "bidirectional"))
      (node (ref "5V_I2C3") (pin "P$2") (pinfunction "P$2_P$2") (pintype "bidirectional"))
      (node (ref "5V_I2C4") (pin "P$2") (pinfunction "P$2_P$2") (pintype "bidirectional"))
      (node (ref "I2C_LEDS") (pin "P$2") (pinfunction "P$2_P$2") (pintype "bidirectional"))
      (node (ref "R2") (pin "1") (pinfunction "1_1") (pintype "passive"))
      (node (ref "U1") (pin "20") (pinfunction "20(SDA)_20") (pintype "bidirectional"))
    )
    (net (code "58") (name "TX0") (class "Default")
      (node (ref "U$4") (pin "P$6") (pinfunction "T6_P$6") (pintype "bidirectional"))
      (node (ref "U1") (pin "1") (pinfunction "1(TX0)_1") (pintype "bidirectional"))
    )
    (net (code "59") (name "TX1") (class "Default")
      (node (ref "R1") (pin "1") (pinfunction "1_1") (pintype "passive"))
      (node (ref "U$4") (pin "P$4") (pinfunction "T4_P$4") (pintype "bidirectional"))
      (node (ref "U1") (pin "18") (pinfunction "18(TX1)_18") (pintype "bidirectional"))
    )
    (net (code "60") (name "TX2") (class "Default")
      (node (ref "U1") (pin "16") (pinfunction "16(TX2)_16") (pintype "bidirectional"))
    )
    (net (code "61") (name "unconnected-(U$3-NC-PadP$1)") (class "Default")
      (node (ref "U$3") (pin "P$1") (pinfunction "NC_P$1") (pintype "bidirectional"))
    )
    (net (code "62") (name "unconnected-(U$3-NC_2-PadP$4)") (class "Default")
      (node (ref "U$3") (pin "P$4") (pinfunction "NC_2_P$4") (pintype "bidirectional"))
    )
    (net (code "63") (name "unconnected-(U$3-NC_3-PadP$6)") (class "Default")
      (node (ref "U$3") (pin "P$6") (pinfunction "NC_3_P$6") (pintype "bidirectional"))
    )
    (net (code "64") (name "unconnected-(U$13-PadP$1)") (class "Default")
      (node (ref "U$13") (pin "P$1") (pinfunction "P$1_P$1") (pintype "bidirectional"))
    )
    (net (code "65") (name "unconnected-(U$14-PadP$1)") (class "Default")
      (node (ref "U$14") (pin "P$1") (pinfunction "P$1_P$1") (pintype "bidirectional"))
    )
    (net (code "66") (name "unconnected-(U$15-PadP$1)") (class "Default")
      (node (ref "U$15") (pin "P$1") (pinfunction "P$1_P$1") (pintype "bidirectional"))
    )
    (net (code "67") (name "unconnected-(U$16-PadP$1)") (class "Default")
      (node (ref "U$16") (pin "P$1") (pinfunction "P$1_P$1") (pintype "bidirectional"))
    )
    (net (code "68") (name "unconnected-(U$17-PadP$1)") (class "Default")
      (node (ref "U$17") (pin "P$1") (pinfunction "P$1_P$1") (pintype "bidirectional"))
    )
    (net (code "69") (name "unconnected-(U$18-PadP$1)") (class "Default")
      (node (ref "U$18") (pin "P$1") (pinfunction "P$1_P$1") (pintype "bidirectional"))
    )
    (net (code "70") (name "unconnected-(U$19-PadP$1)") (class "Default")
      (node (ref "U$19") (pin "P$1") (pinfunction "P$1_P$1") (pintype "bidirectional"))
    )
    (net (code "71") (name "unconnected-(U$20-PadP$1)") (class "Default")
      (node (ref "U$20") (pin "P$1") (pinfunction "P$1_P$1") (pintype "bidirectional"))
    )
    (net (code "72") (name "unconnected-(U$21-PadP$1)") (class "Default")
      (node (ref "U$21") (pin "P$1") (pinfunction "P$1_P$1") (pintype "bidirectional"))
    )
    (net (code "73") (name "unconnected-(U$22-PadP$1)") (class "Default")
      (node (ref "U$22") (pin "P$1") (pinfunction "P$1_P$1") (pintype "bidirectional"))
    )
    (net (code "74") (name "unconnected-(U$23-PadP$1)") (class "Default")
      (node (ref "U$23") (pin "P$1") (pinfunction "P$1_P$1") (pintype "bidirectional"))
    )
    (net (code "75") (name "unconnected-(U$24-PadP$1)") (class "Default")
      (node (ref "U$24") (pin "P$1") (pinfunction "P$1_P$1") (pintype "bidirectional"))
    )
    (net (code "76") (name "unconnected-(U$25-PadP$1)") (class "Default")
      (node (ref "U$25") (pin "P$1") (pinfunction "P$1_P$1") (pintype "bidirectional"))
    )
    (net (code "77") (name "unconnected-(U$26-PadP$1)") (class "Default")
      (node (ref "U$26") (pin "P$1") (pinfunction "P$1_P$1") (pintype "bidirectional"))
    )
    (net (code "78") (name "unconnected-(U$27-PadP$1)") (class "Default")
      (node (ref "U$27") (pin "P$1") (pinfunction "P$1_P$1") (pintype "bidirectional"))
    )
    (net (code "79") (name "unconnected-(U$28-PadP$1)") (class "Default")
      (node (ref "U$28") (pin "P$1") (pinfunction "P$1_P$1") (pintype "bidirectional"))
    )
    (net (code "80") (name "unconnected-(U$29-PadP$1)") (class "Default")
      (node (ref "U$29") (pin "P$1") (pinfunction "P$1_P$1") (pintype "bidirectional"))
    )
    (net (code "81") (name "unconnected-(U$30-PadP$1)") (class "Default")
      (node (ref "U$30") (pin "P$1") (pinfunction "P$1_P$1") (pintype "bidirectional"))
    )
    (net (code "82") (name "unconnected-(U$31-PadP$1)") (class "Default")
      (node (ref "U$31") (pin "P$1") (pinfunction "P$1_P$1") (pintype "bidirectional"))
    )
    (net (code "83") (name "unconnected-(U$32-PadP$1)") (class "Default")
      (node (ref "U$32") (pin "P$1") (pinfunction "P$1_P$1") (pintype "bidirectional"))
    )
    (net (code "84") (name "unconnected-(U$33-PadP$1)") (class "Default")
      (node (ref "U$33") (pin "P$1") (pinfunction "P$1_P$1") (pintype "bidirectional"))
    )
    (net (code "85") (name "unconnected-(U$35-PadP$1)") (class "Default")
      (node (ref "U$35") (pin "P$1") (pinfunction "P$1_P$1") (pintype "bidirectional"))
    )
    (net (code "86") (name "unconnected-(U$36-PadP$1)") (class "Default")
      (node (ref "U$36") (pin "P$1") (pinfunction "P$1_P$1") (pintype "bidirectional"))
    )
    (net (code "87") (name "unconnected-(U$37-PadP$1)") (class "Default")
      (node (ref "U$37") (pin "P$1") (pinfunction "P$1_P$1") (pintype "bidirectional"))
    )
    (net (code "88") (name "unconnected-(U$39-PadP$1)") (class "Default")
      (node (ref "U$39") (pin "P$1") (pinfunction "P$1_P$1") (pintype "bidirectional"))
    )
    (net (code "89") (name "unconnected-(U$40-PadP$1)") (class "Default")
      (node (ref "U$40") (pin "P$1") (pinfunction "P$1_P$1") (pintype "bidirectional"))
    )
    (net (code "90") (name "unconnected-(U$41-PadP$1)") (class "Default")
      (node (ref "U$41") (pin "P$1") (pinfunction "P$1_P$1") (pintype "bidirectional"))
    )
    (net (code "91") (name "unconnected-(U$42-PadP$1)") (class "Default")
      (node (ref "U$42") (pin "P$1") (pinfunction "P$1_P$1") (pintype "bidirectional"))
    )
    (net (code "92") (name "unconnected-(U$43-PadP$1)") (class "Default")
      (node (ref "U$43") (pin "P$1") (pinfunction "P$1_P$1") (pintype "bidirectional"))
    )
    (net (code "93") (name "unconnected-(U$44-PadP$1)") (class "Default")
      (node (ref "U$44") (pin "P$1") (pinfunction "P$1_P$1") (pintype "bidirectional"))
    )
    (net (code "94") (name "unconnected-(U$46-PadP$1)") (class "Default")
      (node (ref "U$46") (pin "P$1") (pinfunction "P$1_P$1") (pintype "bidirectional"))
    )
    (net (code "95") (name "unconnected-(U1-Pad3.3V)") (class "Default")
      (node (ref "U1") (pin "3.3V") (pinfunction "3.3V_3.3V") (pintype "bidirectional"))
    )
    (net (code "96") (name "unconnected-(U1-Pad22)") (class "Default")
      (node (ref "U1") (pin "22") (pinfunction "22_22") (pintype "bidirectional"))
    )
    (net (code "97") (name "unconnected-(U1-Pad24)") (class "Default")
      (node (ref "U1") (pin "24") (pinfunction "24_24") (pintype "bidirectional"))
    )
    (net (code "98") (name "unconnected-(U1-Pad26)") (class "Default")
      (node (ref "U1") (pin "26") (pinfunction "26_26") (pintype "bidirectional"))
    )
    (net (code "99") (name "unconnected-(U1-Pad38)") (class "Default")
      (node (ref "U1") (pin "38") (pinfunction "38_38") (pintype "bidirectional"))
    )
    (net (code "100") (name "unconnected-(U1-Pad40)") (class "Default")
      (node (ref "U1") (pin "40") (pinfunction "40_40") (pintype "bidirectional"))
    )
    (net (code "101") (name "unconnected-(U1-Pad42)") (class "Default")
      (node (ref "U1") (pin "42") (pinfunction "42_42") (pintype "bidirectional"))
    )
    (net (code "102") (name "unconnected-(U1-Pad44)") (class "Default")
      (node (ref "U1") (pin "44") (pinfunction "44_44") (pintype "bidirectional"))
    )
    (net (code "103") (name "unconnected-(U1-Pad46)") (class "Default")
      (node (ref "U1") (pin "46") (pinfunction "46_46") (pintype "bidirectional"))
    )
    (net (code "104") (name "unconnected-(U1-Pad48)") (class "Default")
      (node (ref "U1") (pin "48") (pinfunction "48_48") (pintype "bidirectional"))
    )
    (net (code "105") (name "unconnected-(U1-Pad50)") (class "Default")
      (node (ref "U1") (pin "50") (pinfunction "50_50") (pintype "bidirectional"))
    )
    (net (code "106") (name "unconnected-(U1-Pad52)") (class "Default")
      (node (ref "U1") (pin "52") (pinfunction "52_52") (pintype "bidirectional"))
    )
    (net (code "107") (name "unconnected-(U1-PadAREF)") (class "Default")
      (node (ref "U1") (pin "AREF") (pinfunction "AREF_AREF") (pintype "bidirectional"))
    )
    (net (code "108") (name "unconnected-(U1-PadRESET)") (class "Default")
      (node (ref "U1") (pin "RESET") (pinfunction "RESET_RESET") (pintype "bidirectional"))
    )
  )
)
